# ARKnew.net
KiCad netlist of a schematic drawn in EAGLE
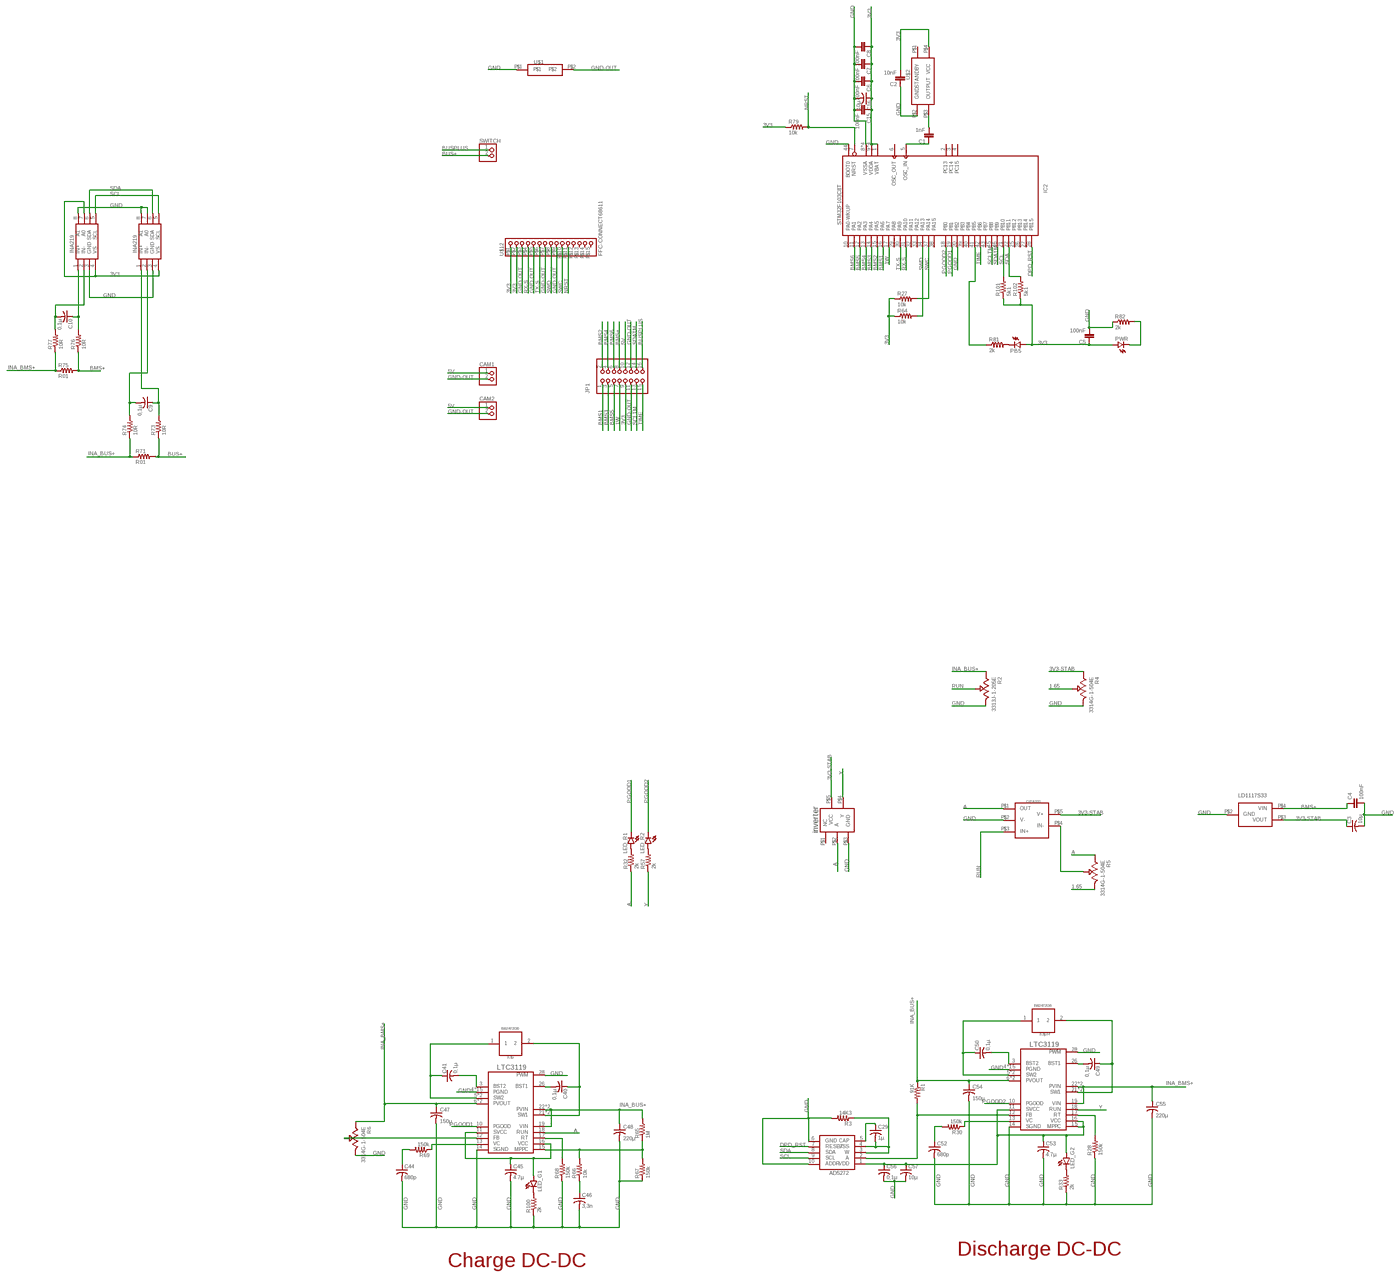
[diagram p0: schematic, sheet 1, overview]
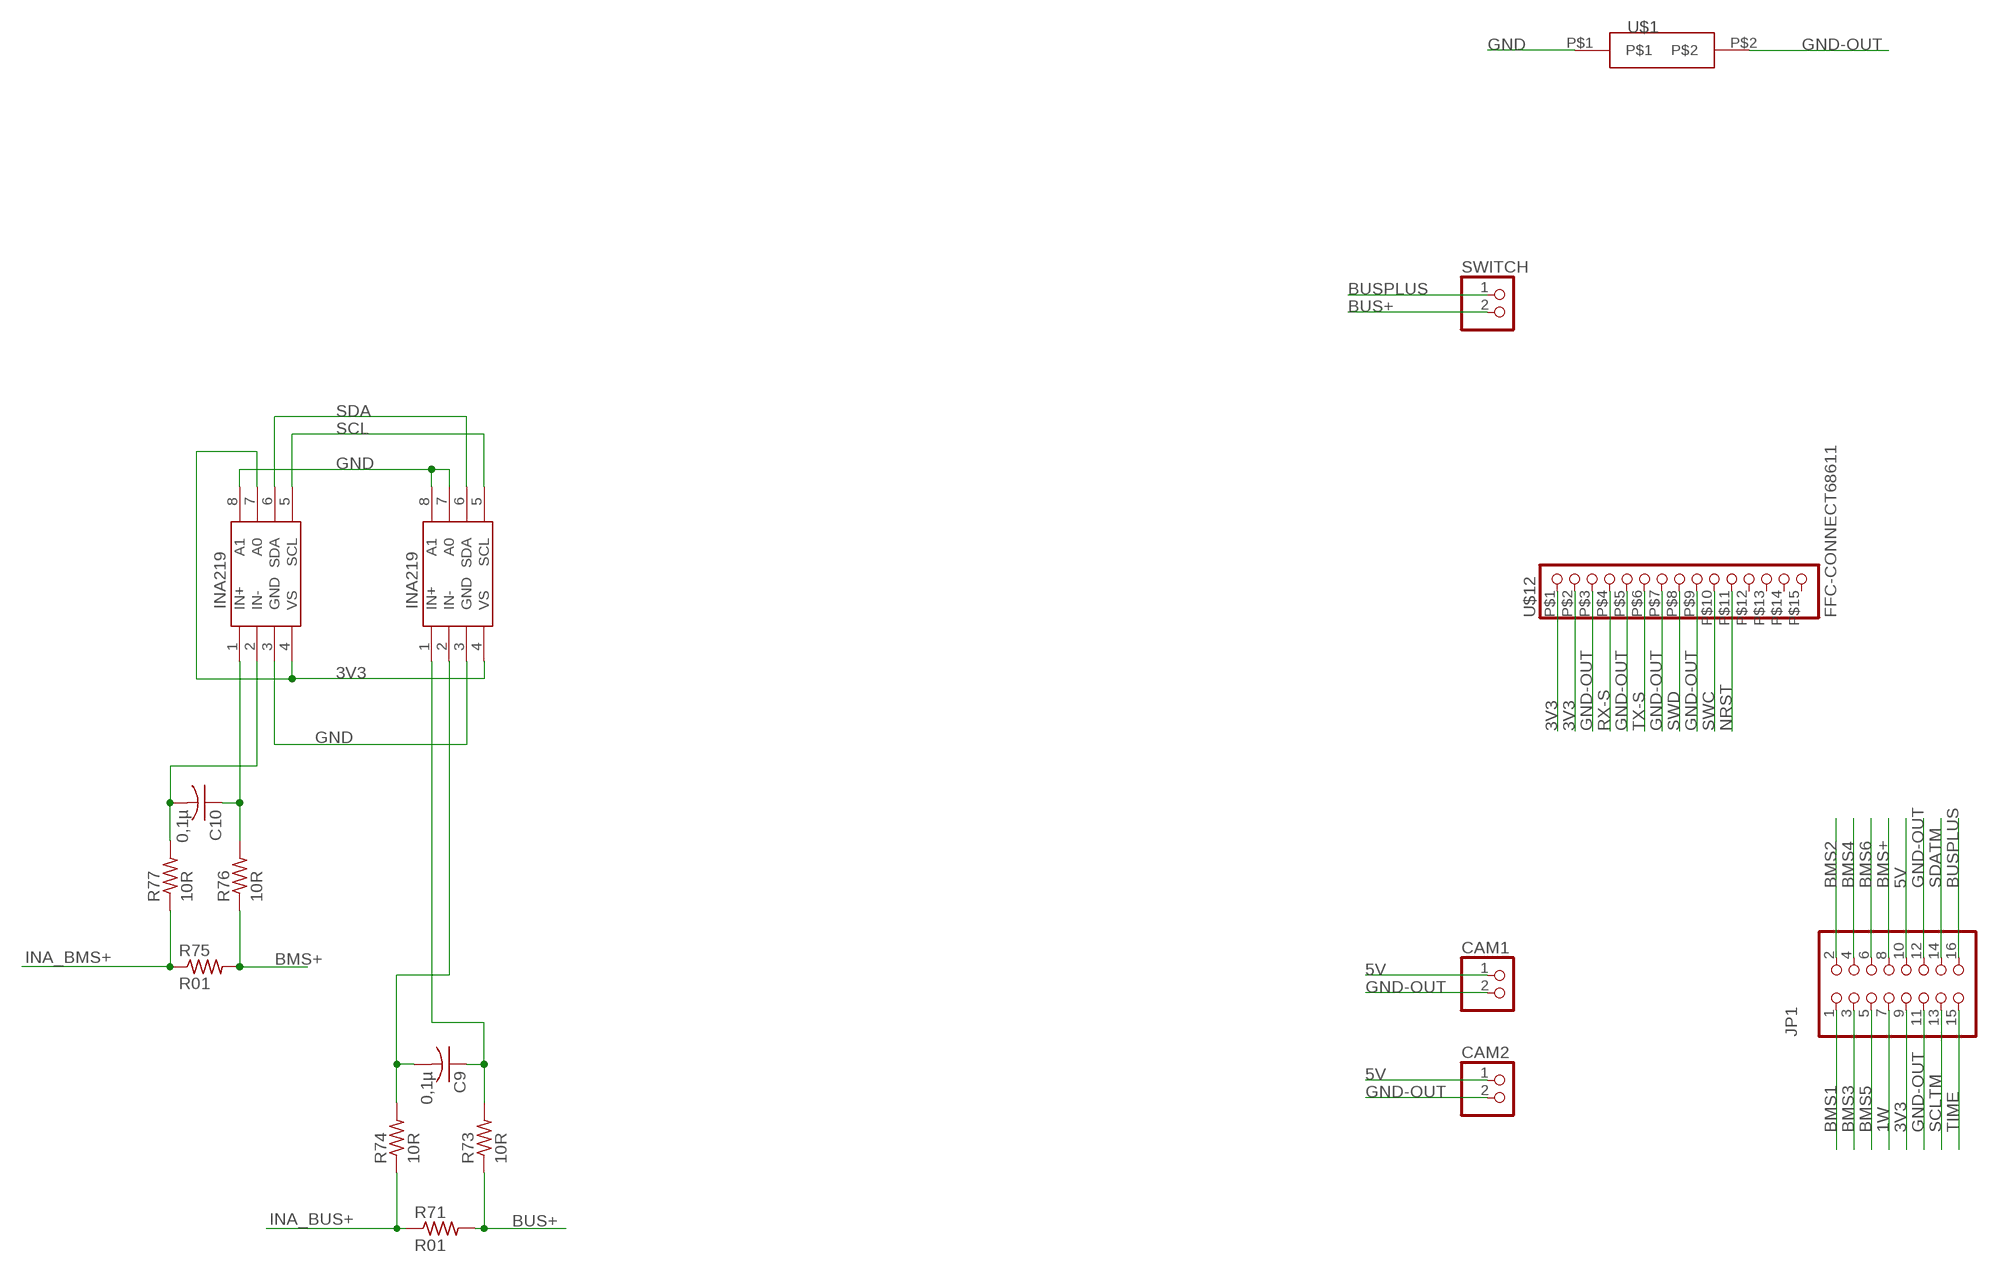
[diagram p1: schematic, sheet 1, part 1 of 4]
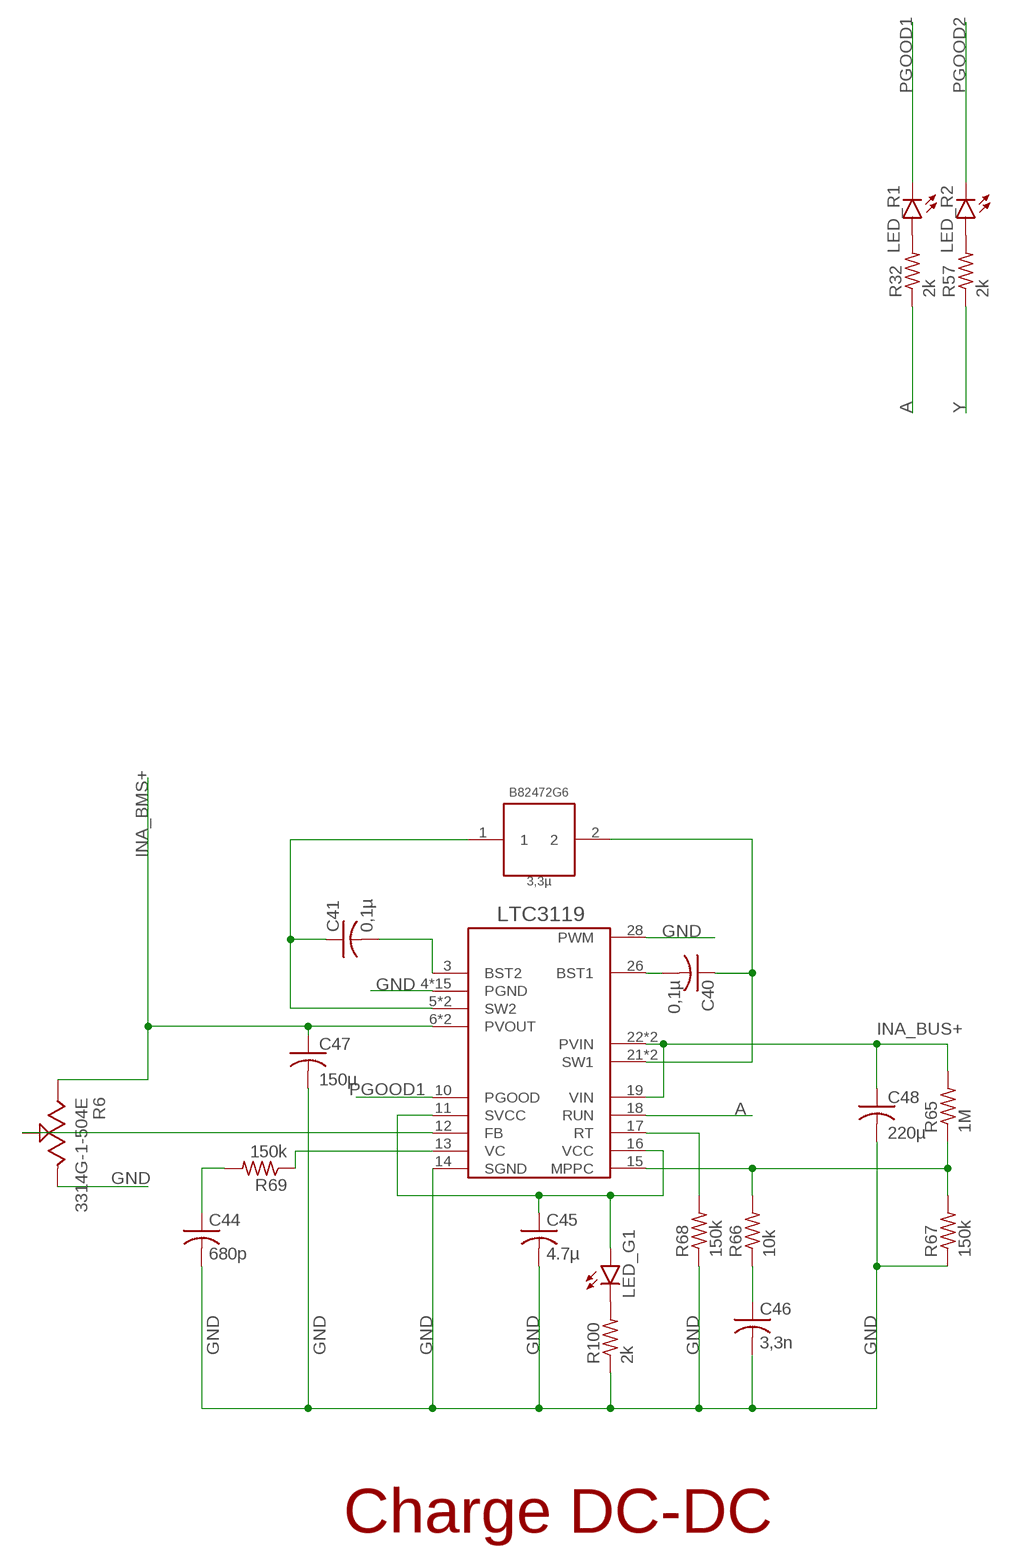
[diagram p2: schematic, sheet 1, part 2 of 4]
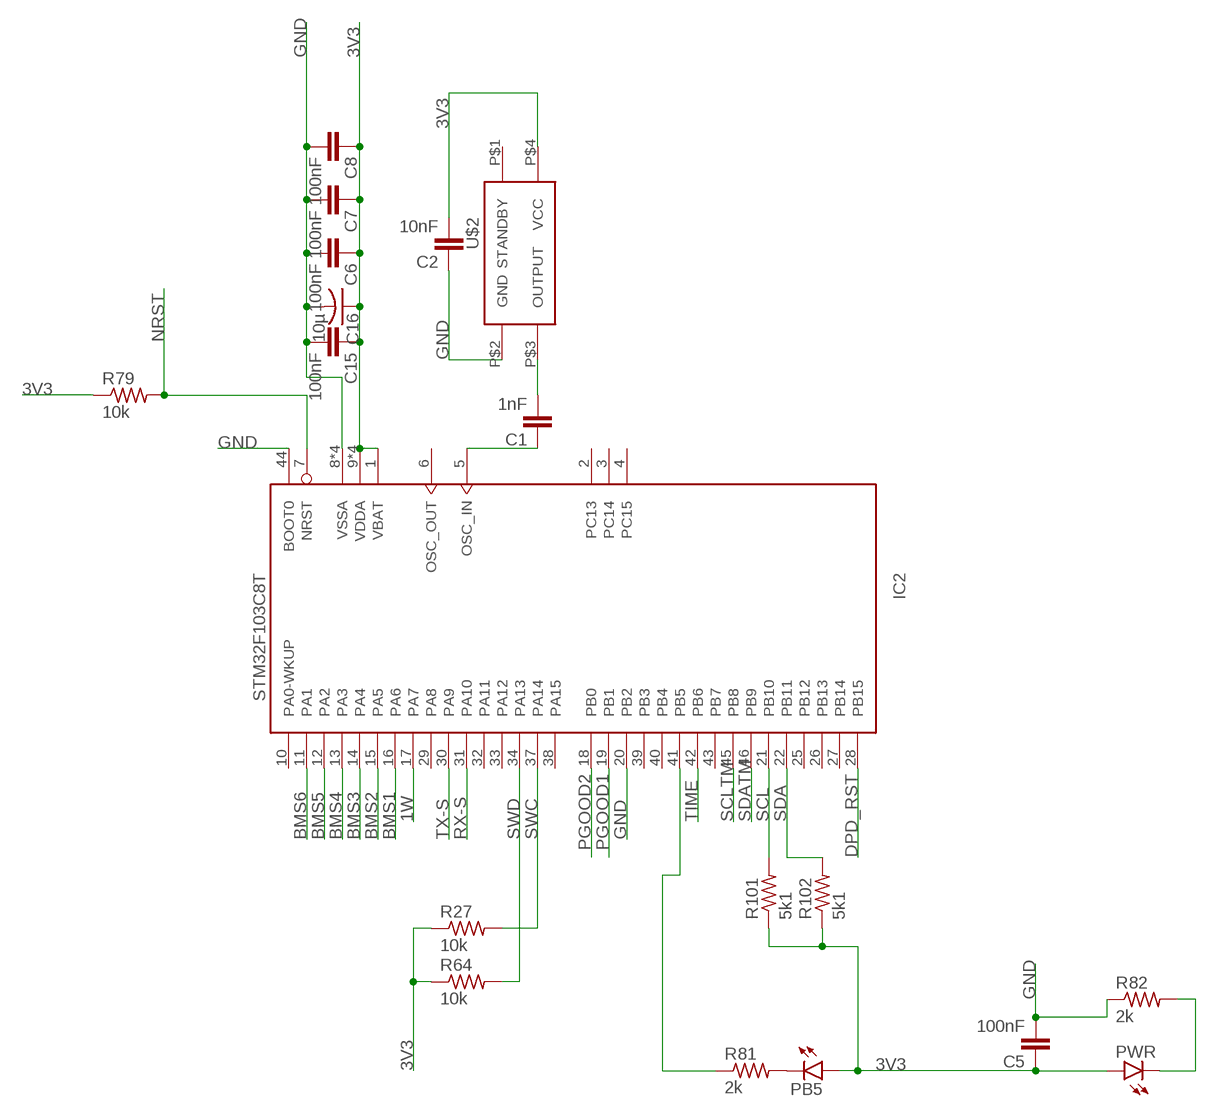
[diagram p3: schematic, sheet 1, part 3 of 4]
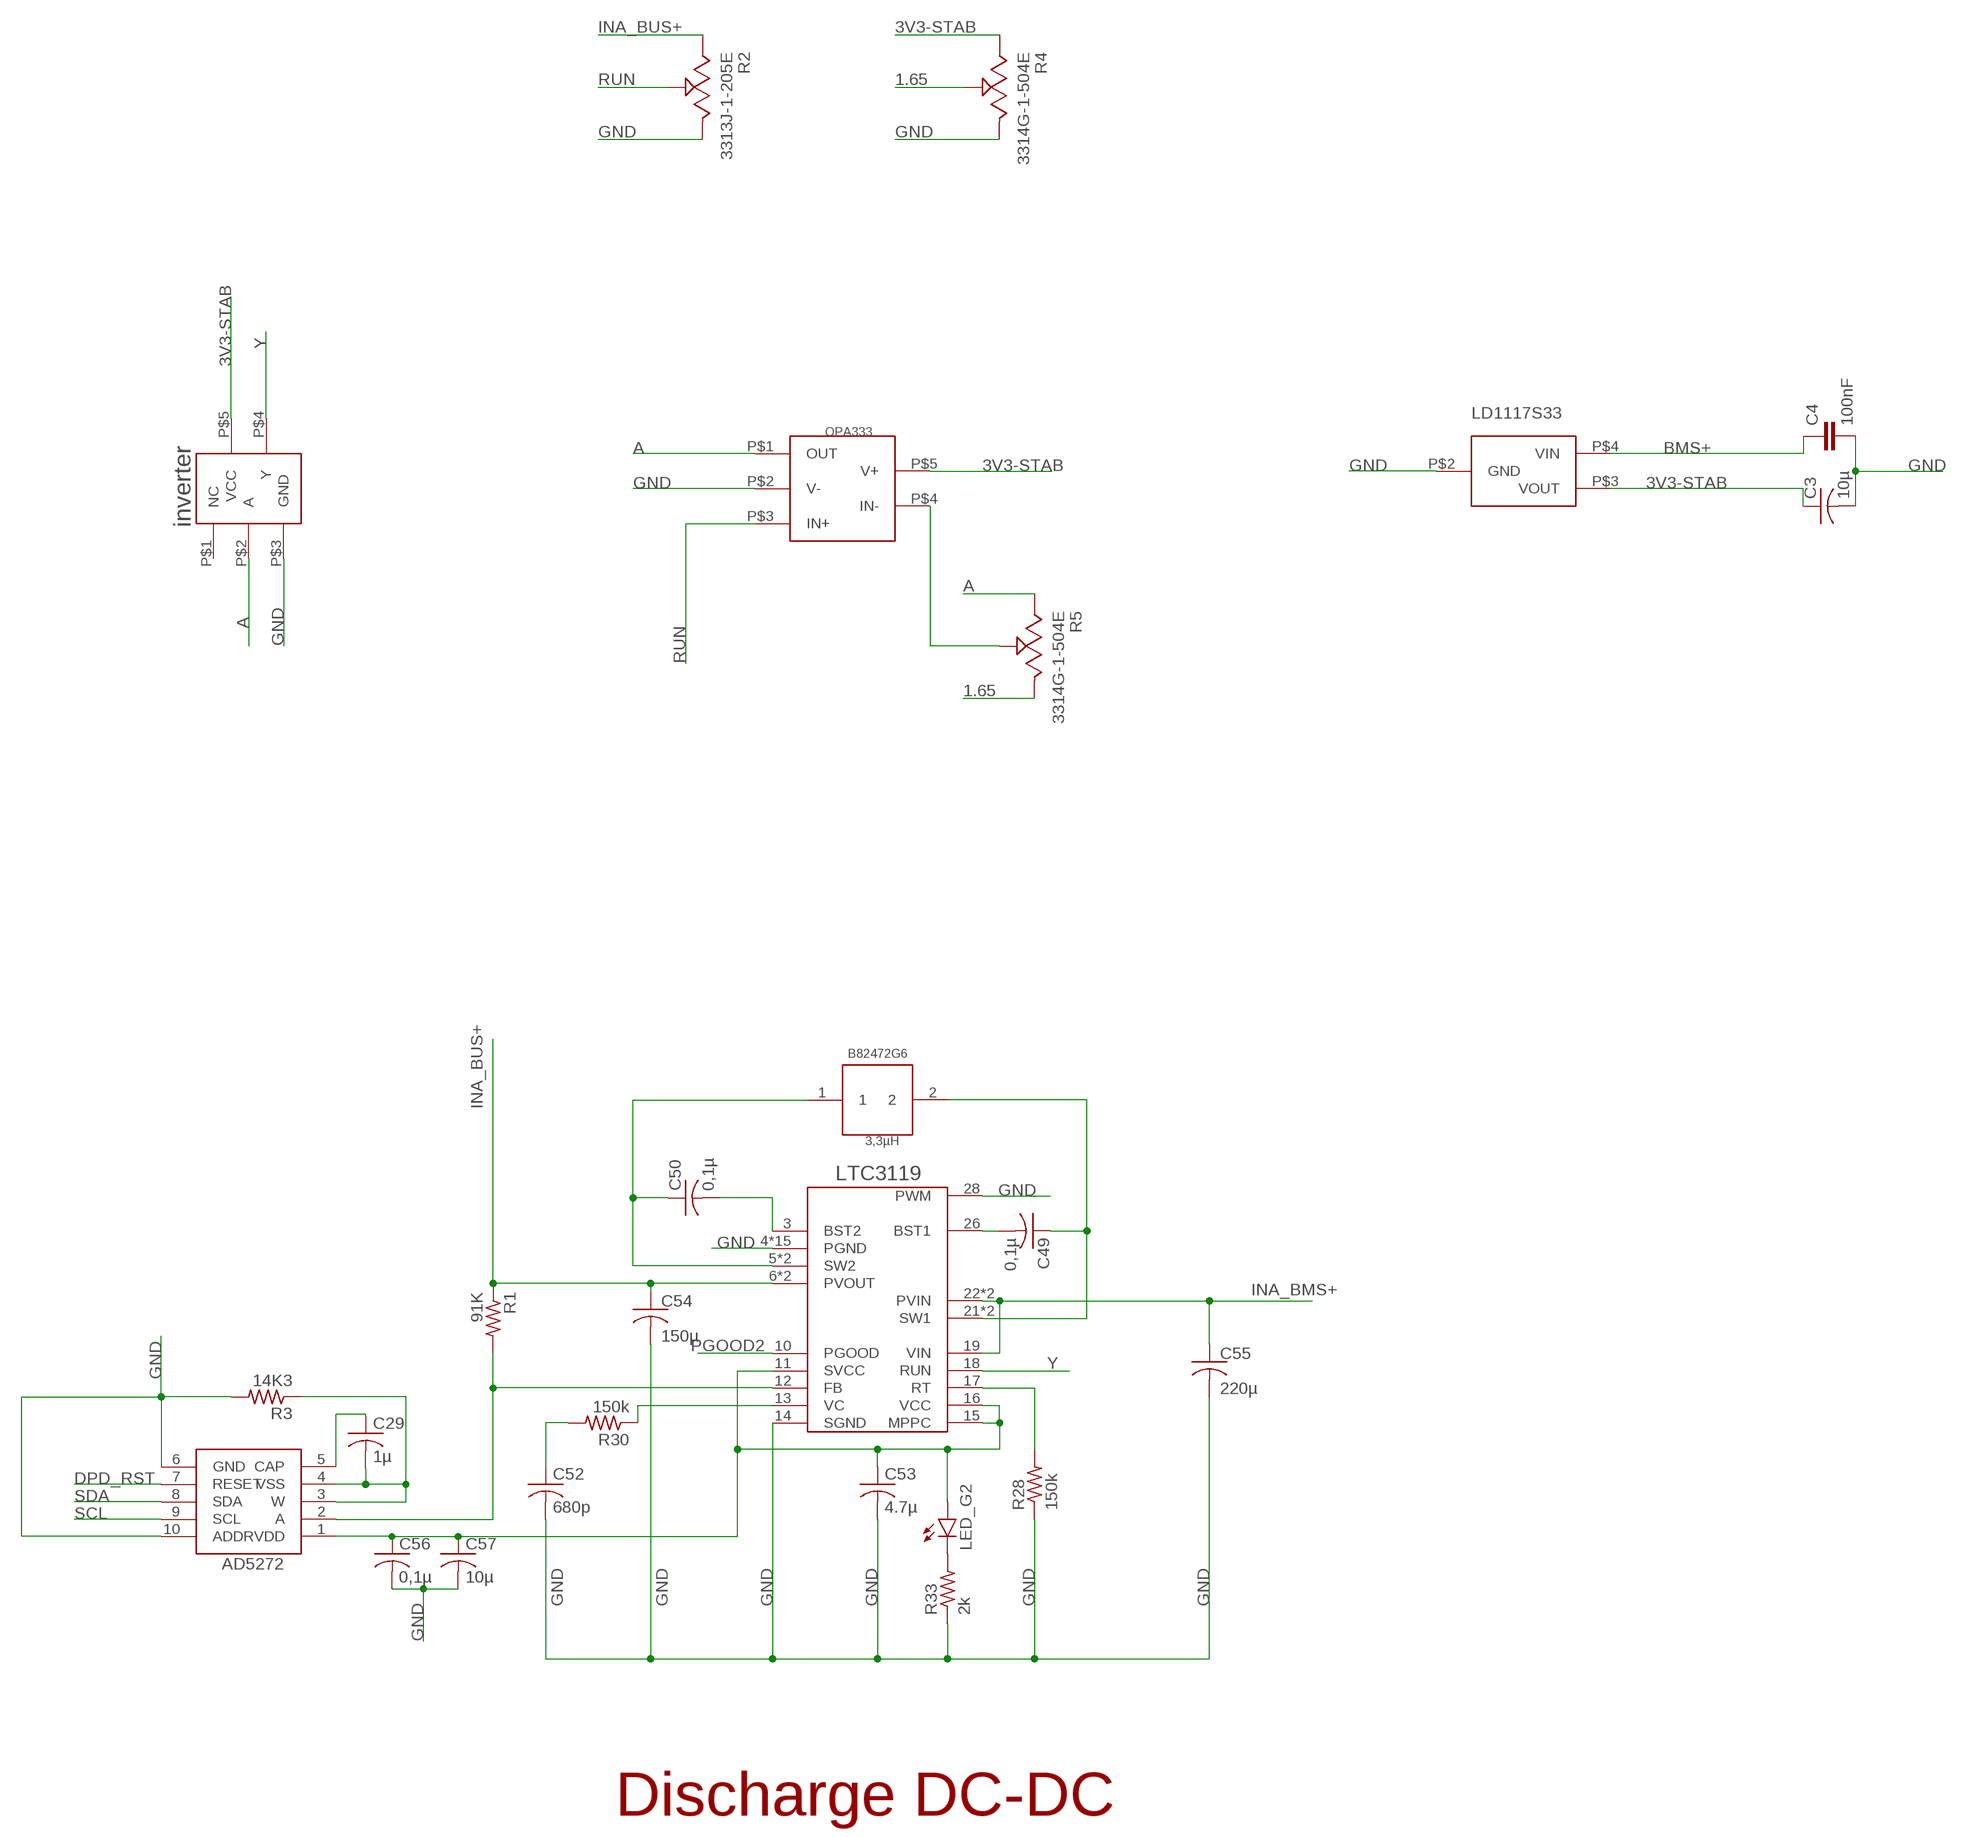
[diagram p4: schematic, sheet 1, part 4 of 4]

(export (version "E")
  (design (tool "Eeschema 10.0.6"))
  (components
    (comp (ref "3,3µH")
      (value "3,3µ")
      (footprint "eagle-import:B82472G6")
      (libsource (lib "eagle-import") (part "B82472G6"))
    )
    (comp (ref "3,3µH1")
      (value "3,3µH")
      (footprint "eagle-import:B82472G6")
      (libsource (lib "eagle-import") (part "B82472G6"))
    )
    (comp (ref "AD5272#2")
      (value "AD5272")
      (footprint "eagle-import:MSOP10")
      (libsource (lib "eagle-import") (part "AD5272"))
    )
    (comp (ref "C1")
      (value "1nF")
      (footprint "eagle-import:C0603")
      (libsource (lib "eagle-import") (part "C-EUC0603"))
    )
    (comp (ref "C2")
      (value "10nF")
      (footprint "eagle-import:C0603")
      (libsource (lib "eagle-import") (part "C-EUC0603"))
    )
    (comp (ref "C3")
      (value "10µ")
      (footprint "eagle-import:C1206")
      (libsource (lib "eagle-import") (part "C-USC1206"))
    )
    (comp (ref "C4")
      (value "100nF")
      (footprint "eagle-import:C0603")
      (libsource (lib "eagle-import") (part "C-EUC0603"))
    )
    (comp (ref "C5")
      (value "100nF")
      (footprint "eagle-import:C0603")
      (libsource (lib "eagle-import") (part "C-EUC0603"))
    )
    (comp (ref "C6")
      (value "100nF")
      (footprint "eagle-import:C0603")
      (libsource (lib "eagle-import") (part "C-EUC0603"))
    )
    (comp (ref "C7")
      (value "100nF")
      (footprint "eagle-import:C0603")
      (libsource (lib "eagle-import") (part "C-EUC0603"))
    )
    (comp (ref "C8")
      (value "100nF")
      (footprint "eagle-import:C0603")
      (libsource (lib "eagle-import") (part "C-EUC0603"))
    )
    (comp (ref "C9")
      (value "0,1µ")
      (footprint "eagle-import:C0603")
      (libsource (lib "eagle-import") (part "C-USC0603"))
    )
    (comp (ref "C10")
      (value "0,1µ")
      (footprint "eagle-import:C0603")
      (libsource (lib "eagle-import") (part "C-USC0603"))
    )
    (comp (ref "C15")
      (value "100nF")
      (footprint "eagle-import:C0603")
      (libsource (lib "eagle-import") (part "C-EUC0603"))
    )
    (comp (ref "C16")
      (value "10µ")
      (footprint "eagle-import:C1206")
      (libsource (lib "eagle-import") (part "C-USC1206"))
    )
    (comp (ref "C29")
      (value "1µ")
      (footprint "eagle-import:C0603")
      (libsource (lib "eagle-import") (part "C-USC0603"))
    )
    (comp (ref "C40")
      (value "0,1µ")
      (footprint "eagle-import:C0603")
      (libsource (lib "eagle-import") (part "C-USC0603"))
    )
    (comp (ref "C41")
      (value "0,1µ")
      (footprint "eagle-import:C0603")
      (libsource (lib "eagle-import") (part "C-USC0603"))
    )
    (comp (ref "C44")
      (value "680p")
      (footprint "eagle-import:C0603")
      (libsource (lib "eagle-import") (part "C-USC0603"))
    )
    (comp (ref "C45")
      (value "4.7µ")
      (footprint "eagle-import:C1206")
      (libsource (lib "eagle-import") (part "C-USC1206"))
    )
    (comp (ref "C46")
      (value "3,3n")
      (footprint "eagle-import:C0603")
      (libsource (lib "eagle-import") (part "C-USC0603"))
    )
    (comp (ref "C47")
      (value "150µ")
      (footprint "eagle-import:ECAP150-CMD")
      (libsource (lib "eagle-import") (part "ECAPECAP150"))
    )
    (comp (ref "C48")
      (value "220µ")
      (footprint "eagle-import:ECAP220-CMD")
      (libsource (lib "eagle-import") (part "ECAPECAP220"))
    )
    (comp (ref "C49")
      (value "0,1µ")
      (footprint "eagle-import:C0603")
      (libsource (lib "eagle-import") (part "C-USC0603"))
    )
    (comp (ref "C50")
      (value "0,1µ")
      (footprint "eagle-import:C0603")
      (libsource (lib "eagle-import") (part "C-USC0603"))
    )
    (comp (ref "C52")
      (value "680p")
      (footprint "eagle-import:C0603")
      (libsource (lib "eagle-import") (part "C-USC0603"))
    )
    (comp (ref "C53")
      (value "4.7µ")
      (footprint "eagle-import:C1206")
      (libsource (lib "eagle-import") (part "C-USC1206"))
    )
    (comp (ref "C54")
      (value "150µ")
      (footprint "eagle-import:ECAP150-CMD")
      (libsource (lib "eagle-import") (part "ECAPECAP150"))
    )
    (comp (ref "C55")
      (value "220µ")
      (footprint "eagle-import:ECAP220-CMD")
      (libsource (lib "eagle-import") (part "ECAPECAP220"))
    )
    (comp (ref "C56")
      (value "0,1µ")
      (footprint "eagle-import:C0603")
      (libsource (lib "eagle-import") (part "C-USC0603"))
    )
    (comp (ref "C57")
      (value "10µ")
      (footprint "eagle-import:C1206")
      (libsource (lib "eagle-import") (part "C-USC1206"))
    )
    (comp (ref "CAM1")
      (value "PINHD-1X2")
      (footprint "eagle-import:1X02")
      (libsource (lib "eagle-import") (part "PINHD-1X2"))
    )
    (comp (ref "CAM2")
      (value "PINHD-1X2")
      (footprint "eagle-import:1X02")
      (libsource (lib "eagle-import") (part "PINHD-1X2"))
    )
    (comp (ref "IC2")
      (value "STM32F103C8T")
      (footprint "eagle-import:LQFP48")
      (libsource (lib "eagle-import") (part "STM32F103CT8"))
    )
    (comp (ref "INA219#1")
      (value "INA219AID")
      (footprint "eagle-import:SOT23-8")
      (libsource (lib "eagle-import") (part "INA219AID"))
    )
    (comp (ref "INVERT")
      (value "INVERTER.")
      (footprint "eagle-import:SC70")
      (libsource (lib "eagle-import") (part "INVERTER."))
    )
    (comp (ref "JP1")
      (value "PINHD-2X8")
      (footprint "eagle-import:2X08")
      (libsource (lib "eagle-import") (part "PINHD-2X8"))
    )
    (comp (ref "LD1117S33")
      (value "LD1117S33")
      (footprint "eagle-import:SOT223")
      (libsource (lib "eagle-import") (part "LD1117S33"))
    )
    (comp (ref "LED_G1")
      (value "LEDCHIPLED_0603")
      (footprint "eagle-import:CHIPLED_0603")
      (libsource (lib "eagle-import") (part "LEDCHIPLED_0603"))
    )
    (comp (ref "LED_G2")
      (value "LEDCHIPLED_0603")
      (footprint "eagle-import:CHIPLED_0603")
      (libsource (lib "eagle-import") (part "LEDCHIPLED_0603"))
    )
    (comp (ref "LED_R1")
      (value "LEDCHIPLED_0603")
      (footprint "eagle-import:CHIPLED_0603")
      (libsource (lib "eagle-import") (part "LEDCHIPLED_0603"))
    )
    (comp (ref "LED_R2")
      (value "LEDCHIPLED_0603")
      (footprint "eagle-import:CHIPLED_0603")
      (libsource (lib "eagle-import") (part "LEDCHIPLED_0603"))
    )
    (comp (ref "OPA")
      (value "OPA333")
      (footprint "eagle-import:SOT23-5")
      (libsource (lib "eagle-import") (part "OPA333"))
    )
    (comp (ref "PB5")
      (value "LEDCHIPLED_0603")
      (footprint "eagle-import:CHIPLED_0603")
      (libsource (lib "eagle-import") (part "LEDCHIPLED_0603"))
    )
    (comp (ref "PWR")
      (value "LEDCHIPLED_0603")
      (footprint "eagle-import:CHIPLED_0603")
      (libsource (lib "eagle-import") (part "LEDCHIPLED_0603"))
    )
    (comp (ref "R1")
      (value "91K")
      (footprint "eagle-import:R0603")
      (libsource (lib "eagle-import") (part "resistor_R-US_R0603"))
    )
    (comp (ref "R2")
      (value "3313J-1-205E")
      (footprint "eagle-import:TRIM_3313J-1-205E")
      (fields (field (name "MF") "Bourns") (field (name "MP") "3313J-1-104E"))
      (libsource (lib "eagle-import") (part "3313J-1-205E"))
    )
    (comp (ref "R3")
      (value "14K3")
      (footprint "eagle-import:R0603")
      (libsource (lib "eagle-import") (part "resistor_R-US_R0603"))
    )
    (comp (ref "R4")
      (value "3314G-1-504E")
      (footprint "eagle-import:TRIM_3314G-1-504E")
      (libsource (lib "eagle-import") (part "3314G-1-504E"))
    )
    (comp (ref "R5")
      (value "3314G-1-504E")
      (footprint "eagle-import:TRIM_3314G-1-504E")
      (libsource (lib "eagle-import") (part "3314G-1-504E"))
    )
    (comp (ref "R6")
      (value "3314G-1-504E")
      (footprint "eagle-import:TRIM_3314G-1-504E")
      (libsource (lib "eagle-import") (part "3314G-1-504E"))
    )
    (comp (ref "R27")
      (value "10k")
      (footprint "eagle-import:R0603")
      (libsource (lib "eagle-import") (part "resistor_R-US_R0603"))
    )
    (comp (ref "R28")
      (value "150k")
      (footprint "eagle-import:R0603")
      (libsource (lib "eagle-import") (part "resistor_R-US_R0603"))
    )
    (comp (ref "R30")
      (value "150k")
      (footprint "eagle-import:R0603")
      (libsource (lib "eagle-import") (part "resistor_R-US_R0603"))
    )
    (comp (ref "R32")
      (value "2k")
      (footprint "eagle-import:R0603")
      (libsource (lib "eagle-import") (part "resistor_R-US_R0603"))
    )
    (comp (ref "R33")
      (value "2k")
      (footprint "eagle-import:R0603")
      (libsource (lib "eagle-import") (part "resistor_R-US_R0603"))
    )
    (comp (ref "R57")
      (value "2k")
      (footprint "eagle-import:R0603")
      (libsource (lib "eagle-import") (part "resistor_R-US_R0603"))
    )
    (comp (ref "R64")
      (value "10k")
      (footprint "eagle-import:R0603")
      (libsource (lib "eagle-import") (part "resistor_R-US_R0603"))
    )
    (comp (ref "R65")
      (value "1M")
      (footprint "eagle-import:R0603")
      (libsource (lib "eagle-import") (part "resistor_R-US_R0603"))
    )
    (comp (ref "R66")
      (value "10k")
      (footprint "eagle-import:R0603")
      (libsource (lib "eagle-import") (part "resistor_R-US_R0603"))
    )
    (comp (ref "R67")
      (value "150k")
      (footprint "eagle-import:R0603")
      (libsource (lib "eagle-import") (part "resistor_R-US_R0603"))
    )
    (comp (ref "R68")
      (value "150k")
      (footprint "eagle-import:R0603")
      (libsource (lib "eagle-import") (part "resistor_R-US_R0603"))
    )
    (comp (ref "R69")
      (value "150k")
      (footprint "eagle-import:R0603")
      (libsource (lib "eagle-import") (part "resistor_R-US_R0603"))
    )
    (comp (ref "R71")
      (value "R01")
      (footprint "eagle-import:R2512")
      (libsource (lib "eagle-import") (part "R-US_R2512"))
    )
    (comp (ref "R73")
      (value "10R")
      (footprint "eagle-import:R0603")
      (libsource (lib "eagle-import") (part "resistor_R-US_R0603"))
    )
    (comp (ref "R74")
      (value "10R")
      (footprint "eagle-import:R0603")
      (libsource (lib "eagle-import") (part "resistor_R-US_R0603"))
    )
    (comp (ref "R75")
      (value "R01")
      (footprint "eagle-import:R2512")
      (libsource (lib "eagle-import") (part "R-US_R2512"))
    )
    (comp (ref "R76")
      (value "10R")
      (footprint "eagle-import:R0603")
      (libsource (lib "eagle-import") (part "resistor_R-US_R0603"))
    )
    (comp (ref "R77")
      (value "10R")
      (footprint "eagle-import:R0603")
      (libsource (lib "eagle-import") (part "resistor_R-US_R0603"))
    )
    (comp (ref "R79")
      (value "10k")
      (footprint "eagle-import:R0603")
      (libsource (lib "eagle-import") (part "resistor_R-US_R0603"))
    )
    (comp (ref "R81")
      (value "2k")
      (footprint "eagle-import:R0603")
      (libsource (lib "eagle-import") (part "resistor_R-US_R0603"))
    )
    (comp (ref "R82")
      (value "2k")
      (footprint "eagle-import:R0603")
      (libsource (lib "eagle-import") (part "resistor_R-US_R0603"))
    )
    (comp (ref "R100")
      (value "2k")
      (footprint "eagle-import:R0603")
      (libsource (lib "eagle-import") (part "resistor_R-US_R0603"))
    )
    (comp (ref "R101")
      (value "5k1")
      (footprint "eagle-import:R0603")
      (libsource (lib "eagle-import") (part "resistor_R-US_R0603"))
    )
    (comp (ref "R102")
      (value "5k1")
      (footprint "eagle-import:R0603")
      (libsource (lib "eagle-import") (part "resistor_R-US_R0603"))
    )
    (comp (ref "SWITCH")
      (value "PINHD-1X2")
      (footprint "eagle-import:1X02")
      (libsource (lib "eagle-import") (part "PINHD-1X2"))
    )
    (comp (ref "U$1")
      (value "MF-R400")
      (footprint "eagle-import:MF-R400")
      (libsource (lib "eagle-import") (part "MF-R400"))
    )
    (comp (ref "U$2")
      (value "Q24")
      (footprint "eagle-import:Q24")
      (libsource (lib "eagle-import") (part "Q24"))
    )
    (comp (ref "U$12")
      (value "FFC-CONNECT68611")
      (footprint "eagle-import:68611")
      (libsource (lib "eagle-import") (part "FFC-CONNECT68611"))
    )
    (comp (ref "U$23")
      (value "LTC31191")
      (footprint "eagle-import:LTC3119+VIA")
      (libsource (lib "eagle-import") (part "LTC31191"))
    )
    (comp (ref "U$57")
      (value "INA219AID")
      (footprint "eagle-import:SOT23-8")
      (libsource (lib "eagle-import") (part "INA219AID"))
    )
    (comp (ref "U$59")
      (value "LTC31191")
      (footprint "eagle-import:LTC3119+VIA")
      (libsource (lib "eagle-import") (part "LTC31191"))
    )
  )
  (nets
    (net (code "1") (name "/1.65") (class "Default")
      (node (ref "R4") (pin "2") (pinfunction "WIPER_2") (pintype "passive"))
      (node (ref "R5") (pin "3") (pinfunction "CW_3") (pintype "passive"))
    )
    (net (code "2") (name "/1W") (class "Default")
      (node (ref "IC2") (pin "17") (pinfunction "PA7_17") (pintype "bidirectional"))
      (node (ref "JP1") (pin "7") (pinfunction "7_7") (pintype "passive"))
    )
    (net (code "3") (name "/3V3") (class "Default")
      (node (ref "C15") (pin "1") (pinfunction "1_1") (pintype "passive"))
      (node (ref "C16") (pin "1") (pinfunction "1_1") (pintype "passive"))
      (node (ref "C2") (pin "2") (pinfunction "2_2") (pintype "passive"))
      (node (ref "C5") (pin "1") (pinfunction "1_1") (pintype "passive"))
      (node (ref "C6") (pin "1") (pinfunction "1_1") (pintype "passive"))
      (node (ref "C7") (pin "1") (pinfunction "1_1") (pintype "passive"))
      (node (ref "C8") (pin "1") (pinfunction "1_1") (pintype "passive"))
      (node (ref "IC2") (pin "1") (pinfunction "VBAT_1") (pintype "power_in"))
      (node (ref "IC2") (pin "24") (pinfunction "VDDA_24") (pintype "power_in"))
      (node (ref "IC2") (pin "36") (pinfunction "VDDA_36") (pintype "power_in"))
      (node (ref "IC2") (pin "48") (pinfunction "VDDA_48") (pintype "power_in"))
      (node (ref "IC2") (pin "9") (pinfunction "VDDA_9") (pintype "power_in"))
      (node (ref "INA219#1") (pin "4") (pinfunction "VS_4") (pintype "bidirectional"))
      (node (ref "JP1") (pin "9") (pinfunction "9_9") (pintype "passive"))
      (node (ref "PB5") (pin "A") (pinfunction "A_A") (pintype "passive"))
      (node (ref "PWR") (pin "A") (pinfunction "A_A") (pintype "passive"))
      (node (ref "R101") (pin "1") (pinfunction "1_1") (pintype "passive"))
      (node (ref "R102") (pin "1") (pinfunction "1_1") (pintype "passive"))
      (node (ref "R27") (pin "1") (pinfunction "1_1") (pintype "passive"))
      (node (ref "R64") (pin "1") (pinfunction "1_1") (pintype "passive"))
      (node (ref "R79") (pin "1") (pinfunction "1_1") (pintype "passive"))
      (node (ref "U$12") (pin "P$1") (pinfunction "1_P$1") (pintype "passive"))
      (node (ref "U$12") (pin "P$2") (pinfunction "2_P$2") (pintype "passive"))
      (node (ref "U$2") (pin "P$4") (pinfunction "VCC_P$4") (pintype "bidirectional"))
      (node (ref "U$57") (pin "4") (pinfunction "VS_4") (pintype "bidirectional"))
      (node (ref "U$57") (pin "7") (pinfunction "A0_7") (pintype "bidirectional"))
    )
    (net (code "4") (name "/3V3-STAB") (class "Default")
      (node (ref "C3") (pin "1") (pinfunction "1_1") (pintype "passive"))
      (node (ref "INVERT") (pin "P$5") (pinfunction "VCC_P$5") (pintype "bidirectional"))
      (node (ref "LD1117S33") (pin "P$3") (pinfunction "VOUT_P$3") (pintype "bidirectional"))
      (node (ref "OPA") (pin "P$5") (pinfunction "V+_P$5") (pintype "bidirectional"))
      (node (ref "R4") (pin "1") (pinfunction "CCW_1") (pintype "passive"))
    )
    (net (code "5") (name "/5V") (class "Default")
      (node (ref "CAM1") (pin "1") (pinfunction "1_1") (pintype "passive"))
      (node (ref "CAM2") (pin "1") (pinfunction "1_1") (pintype "passive"))
      (node (ref "JP1") (pin "10") (pinfunction "10_10") (pintype "passive"))
    )
    (net (code "6") (name "/A") (class "Default")
      (node (ref "INVERT") (pin "P$2") (pinfunction "A_P$2") (pintype "bidirectional"))
      (node (ref "OPA") (pin "P$1") (pinfunction "OUT_P$1") (pintype "bidirectional"))
      (node (ref "R32") (pin "1") (pinfunction "1_1") (pintype "passive"))
      (node (ref "R5") (pin "1") (pinfunction "CCW_1") (pintype "passive"))
      (node (ref "U$59") (pin "18") (pinfunction "RUN_18") (pintype "bidirectional"))
    )
    (net (code "7") (name "/BMS+") (class "Default")
      (node (ref "C4") (pin "1") (pinfunction "1_1") (pintype "passive"))
      (node (ref "JP1") (pin "8") (pinfunction "8_8") (pintype "passive"))
      (node (ref "LD1117S33") (pin "P$4") (pinfunction "VIN_P$4") (pintype "bidirectional"))
      (node (ref "R75") (pin "2") (pinfunction "2_2") (pintype "passive"))
      (node (ref "R76") (pin "1") (pinfunction "1_1") (pintype "passive"))
    )
    (net (code "8") (name "/BMS1") (class "Default")
      (node (ref "IC2") (pin "16") (pinfunction "PA6_16") (pintype "bidirectional"))
      (node (ref "JP1") (pin "1") (pinfunction "1_1") (pintype "passive"))
    )
    (net (code "9") (name "/BMS2") (class "Default")
      (node (ref "IC2") (pin "15") (pinfunction "PA5_15") (pintype "bidirectional"))
      (node (ref "JP1") (pin "2") (pinfunction "2_2") (pintype "passive"))
    )
    (net (code "10") (name "/BMS3") (class "Default")
      (node (ref "IC2") (pin "14") (pinfunction "PA4_14") (pintype "bidirectional"))
      (node (ref "JP1") (pin "3") (pinfunction "3_3") (pintype "passive"))
    )
    (net (code "11") (name "/BMS4") (class "Default")
      (node (ref "IC2") (pin "13") (pinfunction "PA3_13") (pintype "bidirectional"))
      (node (ref "JP1") (pin "4") (pinfunction "4_4") (pintype "passive"))
    )
    (net (code "12") (name "/BMS5") (class "Default")
      (node (ref "IC2") (pin "12") (pinfunction "PA2_12") (pintype "bidirectional"))
      (node (ref "JP1") (pin "5") (pinfunction "5_5") (pintype "passive"))
    )
    (net (code "13") (name "/BMS6") (class "Default")
      (node (ref "IC2") (pin "11") (pinfunction "PA1_11") (pintype "bidirectional"))
      (node (ref "JP1") (pin "6") (pinfunction "6_6") (pintype "passive"))
    )
    (net (code "14") (name "/BUS+") (class "Default")
      (node (ref "R71") (pin "2") (pinfunction "2_2") (pintype "passive"))
      (node (ref "R73") (pin "1") (pinfunction "1_1") (pintype "passive"))
      (node (ref "SWITCH") (pin "2") (pinfunction "2_2") (pintype "passive"))
    )
    (net (code "15") (name "/BUSPLUS") (class "Default")
      (node (ref "JP1") (pin "16") (pinfunction "16_16") (pintype "passive"))
      (node (ref "SWITCH") (pin "1") (pinfunction "1_1") (pintype "passive"))
    )
    (net (code "16") (name "/DPD_RST") (class "Default")
      (node (ref "AD5272#2") (pin "7") (pinfunction "RESET_7") (pintype "bidirectional"))
      (node (ref "IC2") (pin "28") (pinfunction "PB15_28") (pintype "bidirectional"))
    )
    (net (code "17") (name "/GND") (class "Default")
      (node (ref "AD5272#2") (pin "10") (pinfunction "ADDR_10") (pintype "bidirectional"))
      (node (ref "AD5272#2") (pin "6") (pinfunction "GND_6") (pintype "bidirectional"))
      (node (ref "C15") (pin "2") (pinfunction "2_2") (pintype "passive"))
      (node (ref "C16") (pin "2") (pinfunction "2_2") (pintype "passive"))
      (node (ref "C2") (pin "1") (pinfunction "1_1") (pintype "passive"))
      (node (ref "C3") (pin "2") (pinfunction "2_2") (pintype "passive"))
      (node (ref "C4") (pin "2") (pinfunction "2_2") (pintype "passive"))
      (node (ref "C44") (pin "2") (pinfunction "2_2") (pintype "passive"))
      (node (ref "C45") (pin "2") (pinfunction "2_2") (pintype "passive"))
      (node (ref "C46") (pin "2") (pinfunction "2_2") (pintype "passive"))
      (node (ref "C47") (pin "P$2") (pinfunction "2_P$2") (pintype "passive"))
      (node (ref "C48") (pin "P$2") (pinfunction "2_P$2") (pintype "passive"))
      (node (ref "C5") (pin "2") (pinfunction "2_2") (pintype "passive"))
      (node (ref "C52") (pin "2") (pinfunction "2_2") (pintype "passive"))
      (node (ref "C53") (pin "2") (pinfunction "2_2") (pintype "passive"))
      (node (ref "C54") (pin "P$2") (pinfunction "2_P$2") (pintype "passive"))
      (node (ref "C55") (pin "P$2") (pinfunction "2_P$2") (pintype "passive"))
      (node (ref "C56") (pin "2") (pinfunction "2_2") (pintype "passive"))
      (node (ref "C57") (pin "2") (pinfunction "2_2") (pintype "passive"))
      (node (ref "C6") (pin "2") (pinfunction "2_2") (pintype "passive"))
      (node (ref "C7") (pin "2") (pinfunction "2_2") (pintype "passive"))
      (node (ref "C8") (pin "2") (pinfunction "2_2") (pintype "passive"))
      (node (ref "IC2") (pin "20") (pinfunction "PB2_20") (pintype "bidirectional"))
      (node (ref "IC2") (pin "23") (pinfunction "VSSA_23") (pintype "power_in"))
      (node (ref "IC2") (pin "35") (pinfunction "VSSA_35") (pintype "power_in"))
      (node (ref "IC2") (pin "44") (pinfunction "BOOT0_44") (pintype "input"))
      (node (ref "IC2") (pin "47") (pinfunction "VSSA_47") (pintype "power_in"))
      (node (ref "IC2") (pin "8") (pinfunction "VSSA_8") (pintype "power_in"))
      (node (ref "INA219#1") (pin "3") (pinfunction "GND_3") (pintype "bidirectional"))
      (node (ref "INA219#1") (pin "7") (pinfunction "A0_7") (pintype "bidirectional"))
      (node (ref "INA219#1") (pin "8") (pinfunction "A1_8") (pintype "bidirectional"))
      (node (ref "INVERT") (pin "P$3") (pinfunction "GND_P$3") (pintype "bidirectional"))
      (node (ref "LD1117S33") (pin "P$2") (pinfunction "GND_P$2") (pintype "bidirectional"))
      (node (ref "OPA") (pin "P$2") (pinfunction "V-_P$2") (pintype "bidirectional"))
      (node (ref "R100") (pin "1") (pinfunction "1_1") (pintype "passive"))
      (node (ref "R2") (pin "3") (pinfunction "CW_3") (pintype "passive"))
      (node (ref "R28") (pin "1") (pinfunction "1_1") (pintype "passive"))
      (node (ref "R3") (pin "2") (pinfunction "2_2") (pintype "passive"))
      (node (ref "R33") (pin "1") (pinfunction "1_1") (pintype "passive"))
      (node (ref "R4") (pin "3") (pinfunction "CW_3") (pintype "passive"))
      (node (ref "R6") (pin "3") (pinfunction "CW_3") (pintype "passive"))
      (node (ref "R67") (pin "1") (pinfunction "1_1") (pintype "passive"))
      (node (ref "R68") (pin "1") (pinfunction "1_1") (pintype "passive"))
      (node (ref "R82") (pin "1") (pinfunction "1_1") (pintype "passive"))
      (node (ref "U$1") (pin "P$1") (pinfunction "P$1_P$1") (pintype "bidirectional"))
      (node (ref "U$2") (pin "P$2") (pinfunction "GND_P$2") (pintype "bidirectional"))
      (node (ref "U$23") (pin "14") (pinfunction "SGND_14") (pintype "bidirectional"))
      (node (ref "U$23") (pin "20") (pinfunction "PGND_20") (pintype "bidirectional"))
      (node (ref "U$23") (pin "25") (pinfunction "PGND_25") (pintype "bidirectional"))
      (node (ref "U$23") (pin "28") (pinfunction "PWM_28") (pintype "bidirectional"))
      (node (ref "U$23") (pin "29") (pinfunction "PGND_29") (pintype "bidirectional"))
      (node (ref "U$23") (pin "4") (pinfunction "PGND_4") (pintype "bidirectional"))
      (node (ref "U$23") (pin "9") (pinfunction "PGND_9") (pintype "bidirectional"))
      (node (ref "U$23") (pin "P$1") (pinfunction "PGND_P$1") (pintype "bidirectional"))
      (node (ref "U$23") (pin "P$10") (pinfunction "PGND_P$10") (pintype "bidirectional"))
      (node (ref "U$23") (pin "P$2") (pinfunction "PGND_P$2") (pintype "bidirectional"))
      (node (ref "U$23") (pin "P$3") (pinfunction "PGND_P$3") (pintype "bidirectional"))
      (node (ref "U$23") (pin "P$4") (pinfunction "PGND_P$4") (pintype "bidirectional"))
      (node (ref "U$23") (pin "P$5") (pinfunction "PGND_P$5") (pintype "bidirectional"))
      (node (ref "U$23") (pin "P$6") (pinfunction "PGND_P$6") (pintype "bidirectional"))
      (node (ref "U$23") (pin "P$7") (pinfunction "PGND_P$7") (pintype "bidirectional"))
      (node (ref "U$23") (pin "P$8") (pinfunction "PGND_P$8") (pintype "bidirectional"))
      (node (ref "U$23") (pin "P$9") (pinfunction "PGND_P$9") (pintype "bidirectional"))
      (node (ref "U$57") (pin "3") (pinfunction "GND_3") (pintype "bidirectional"))
      (node (ref "U$57") (pin "8") (pinfunction "A1_8") (pintype "bidirectional"))
      (node (ref "U$59") (pin "14") (pinfunction "SGND_14") (pintype "bidirectional"))
      (node (ref "U$59") (pin "20") (pinfunction "PGND_20") (pintype "bidirectional"))
      (node (ref "U$59") (pin "25") (pinfunction "PGND_25") (pintype "bidirectional"))
      (node (ref "U$59") (pin "28") (pinfunction "PWM_28") (pintype "bidirectional"))
      (node (ref "U$59") (pin "29") (pinfunction "PGND_29") (pintype "bidirectional"))
      (node (ref "U$59") (pin "4") (pinfunction "PGND_4") (pintype "bidirectional"))
      (node (ref "U$59") (pin "9") (pinfunction "PGND_9") (pintype "bidirectional"))
      (node (ref "U$59") (pin "P$1") (pinfunction "PGND_P$1") (pintype "bidirectional"))
      (node (ref "U$59") (pin "P$10") (pinfunction "PGND_P$10") (pintype "bidirectional"))
      (node (ref "U$59") (pin "P$2") (pinfunction "PGND_P$2") (pintype "bidirectional"))
      (node (ref "U$59") (pin "P$3") (pinfunction "PGND_P$3") (pintype "bidirectional"))
      (node (ref "U$59") (pin "P$4") (pinfunction "PGND_P$4") (pintype "bidirectional"))
      (node (ref "U$59") (pin "P$5") (pinfunction "PGND_P$5") (pintype "bidirectional"))
      (node (ref "U$59") (pin "P$6") (pinfunction "PGND_P$6") (pintype "bidirectional"))
      (node (ref "U$59") (pin "P$7") (pinfunction "PGND_P$7") (pintype "bidirectional"))
      (node (ref "U$59") (pin "P$8") (pinfunction "PGND_P$8") (pintype "bidirectional"))
      (node (ref "U$59") (pin "P$9") (pinfunction "PGND_P$9") (pintype "bidirectional"))
    )
    (net (code "18") (name "/GND-OUT") (class "Default")
      (node (ref "CAM1") (pin "2") (pinfunction "2_2") (pintype "passive"))
      (node (ref "CAM2") (pin "2") (pinfunction "2_2") (pintype "passive"))
      (node (ref "JP1") (pin "11") (pinfunction "11_11") (pintype "passive"))
      (node (ref "JP1") (pin "12") (pinfunction "12_12") (pintype "passive"))
      (node (ref "U$1") (pin "P$2") (pinfunction "P$2_P$2") (pintype "bidirectional"))
      (node (ref "U$12") (pin "P$3") (pinfunction "3_P$3") (pintype "passive"))
      (node (ref "U$12") (pin "P$5") (pinfunction "5_P$5") (pintype "passive"))
      (node (ref "U$12") (pin "P$7") (pinfunction "7_P$7") (pintype "passive"))
      (node (ref "U$12") (pin "P$9") (pinfunction "9_P$9") (pintype "passive"))
    )
    (net (code "19") (name "/INA_BMS+") (class "Default")
      (node (ref "C47") (pin "P$1") (pinfunction "1_P$1") (pintype "passive"))
      (node (ref "C55") (pin "P$1") (pinfunction "1_P$1") (pintype "passive"))
      (node (ref "R6") (pin "1") (pinfunction "CCW_1") (pintype "passive"))
      (node (ref "R75") (pin "1") (pinfunction "1_1") (pintype "passive"))
      (node (ref "R77") (pin "1") (pinfunction "1_1") (pintype "passive"))
      (node (ref "U$23") (pin "19") (pinfunction "VIN_19") (pintype "bidirectional"))
      (node (ref "U$23") (pin "22") (pinfunction "PVIN_22") (pintype "bidirectional"))
      (node (ref "U$23") (pin "23") (pinfunction "PVIN_23") (pintype "bidirectional"))
      (node (ref "U$59") (pin "6") (pinfunction "PVOUT_6") (pintype "bidirectional"))
      (node (ref "U$59") (pin "7") (pinfunction "PVOUT_7") (pintype "bidirectional"))
    )
    (net (code "20") (name "/INA_BUS+") (class "Default")
      (node (ref "C48") (pin "P$1") (pinfunction "1_P$1") (pintype "passive"))
      (node (ref "C54") (pin "P$1") (pinfunction "1_P$1") (pintype "passive"))
      (node (ref "R1") (pin "1") (pinfunction "1_1") (pintype "passive"))
      (node (ref "R2") (pin "1") (pinfunction "CCW_1") (pintype "passive"))
      (node (ref "R65") (pin "2") (pinfunction "2_2") (pintype "passive"))
      (node (ref "R71") (pin "1") (pinfunction "1_1") (pintype "passive"))
      (node (ref "R74") (pin "1") (pinfunction "1_1") (pintype "passive"))
      (node (ref "U$23") (pin "6") (pinfunction "PVOUT_6") (pintype "bidirectional"))
      (node (ref "U$23") (pin "7") (pinfunction "PVOUT_7") (pintype "bidirectional"))
      (node (ref "U$59") (pin "19") (pinfunction "VIN_19") (pintype "bidirectional"))
      (node (ref "U$59") (pin "22") (pinfunction "PVIN_22") (pintype "bidirectional"))
      (node (ref "U$59") (pin "23") (pinfunction "PVIN_23") (pintype "bidirectional"))
    )
    (net (code "21") (name "/NRST") (class "Default")
      (node (ref "IC2") (pin "7") (pinfunction "NRST_7") (pintype "bidirectional"))
      (node (ref "R79") (pin "2") (pinfunction "2_2") (pintype "passive"))
      (node (ref "U$12") (pin "P$11") (pinfunction "11_P$11") (pintype "passive"))
    )
    (net (code "22") (name "/PGOOD1") (class "Default")
      (node (ref "IC2") (pin "19") (pinfunction "PB1_19") (pintype "bidirectional"))
      (node (ref "LED_R1") (pin "C") (pinfunction "C_C") (pintype "passive"))
      (node (ref "U$59") (pin "10") (pinfunction "PGOOD_10") (pintype "bidirectional"))
    )
    (net (code "23") (name "/PGOOD2") (class "Default")
      (node (ref "IC2") (pin "18") (pinfunction "PB0_18") (pintype "bidirectional"))
      (node (ref "LED_R2") (pin "C") (pinfunction "C_C") (pintype "passive"))
      (node (ref "U$23") (pin "10") (pinfunction "PGOOD_10") (pintype "bidirectional"))
    )
    (net (code "24") (name "/RUN") (class "Default")
      (node (ref "OPA") (pin "P$3") (pinfunction "IN+_P$3") (pintype "bidirectional"))
      (node (ref "R2") (pin "2") (pinfunction "WIPER_2") (pintype "passive"))
    )
    (net (code "25") (name "/RX-S") (class "Default")
      (node (ref "IC2") (pin "31") (pinfunction "PA10_31") (pintype "bidirectional"))
      (node (ref "U$12") (pin "P$4") (pinfunction "4_P$4") (pintype "passive"))
    )
    (net (code "26") (name "/SCL") (class "Default")
      (node (ref "AD5272#2") (pin "9") (pinfunction "SCL_9") (pintype "bidirectional"))
      (node (ref "IC2") (pin "21") (pinfunction "PB10_21") (pintype "bidirectional"))
      (node (ref "INA219#1") (pin "5") (pinfunction "SCL_5") (pintype "bidirectional"))
      (node (ref "R101") (pin "2") (pinfunction "2_2") (pintype "passive"))
      (node (ref "U$57") (pin "5") (pinfunction "SCL_5") (pintype "bidirectional"))
    )
    (net (code "27") (name "/SCLTM") (class "Default")
      (node (ref "IC2") (pin "45") (pinfunction "PB8_45") (pintype "bidirectional"))
      (node (ref "JP1") (pin "13") (pinfunction "13_13") (pintype "passive"))
    )
    (net (code "28") (name "/SDA") (class "Default")
      (node (ref "AD5272#2") (pin "8") (pinfunction "SDA_8") (pintype "bidirectional"))
      (node (ref "IC2") (pin "22") (pinfunction "PB11_22") (pintype "bidirectional"))
      (node (ref "INA219#1") (pin "6") (pinfunction "SDA_6") (pintype "bidirectional"))
      (node (ref "R102") (pin "2") (pinfunction "2_2") (pintype "passive"))
      (node (ref "U$57") (pin "6") (pinfunction "SDA_6") (pintype "bidirectional"))
    )
    (net (code "29") (name "/SDATM") (class "Default")
      (node (ref "IC2") (pin "46") (pinfunction "PB9_46") (pintype "bidirectional"))
      (node (ref "JP1") (pin "14") (pinfunction "14_14") (pintype "passive"))
    )
    (net (code "30") (name "/SWC") (class "Default")
      (node (ref "IC2") (pin "37") (pinfunction "PA14_37") (pintype "bidirectional"))
      (node (ref "R27") (pin "2") (pinfunction "2_2") (pintype "passive"))
      (node (ref "U$12") (pin "P$10") (pinfunction "10_P$10") (pintype "passive"))
    )
    (net (code "31") (name "/SWD") (class "Default")
      (node (ref "IC2") (pin "34") (pinfunction "PA13_34") (pintype "bidirectional"))
      (node (ref "R64") (pin "2") (pinfunction "2_2") (pintype "passive"))
      (node (ref "U$12") (pin "P$8") (pinfunction "8_P$8") (pintype "passive"))
    )
    (net (code "32") (name "/TIME") (class "Default")
      (node (ref "IC2") (pin "42") (pinfunction "PB6_42") (pintype "bidirectional"))
      (node (ref "JP1") (pin "15") (pinfunction "15_15") (pintype "passive"))
    )
    (net (code "33") (name "/TX-S") (class "Default")
      (node (ref "IC2") (pin "30") (pinfunction "PA9_30") (pintype "bidirectional"))
      (node (ref "U$12") (pin "P$6") (pinfunction "6_P$6") (pintype "passive"))
    )
    (net (code "34") (name "/Y") (class "Default")
      (node (ref "INVERT") (pin "P$4") (pinfunction "Y_P$4") (pintype "bidirectional"))
      (node (ref "R57") (pin "1") (pinfunction "1_1") (pintype "passive"))
      (node (ref "U$23") (pin "18") (pinfunction "RUN_18") (pintype "bidirectional"))
    )
    (net (code "35") (name "Net-(3,3µH-Pad1)") (class "Default")
      (node (ref "3,3µH") (pin "1") (pinfunction "1_1") (pintype "bidirectional"))
      (node (ref "C41") (pin "1") (pinfunction "1_1") (pintype "passive"))
      (node (ref "U$59") (pin "5") (pinfunction "SW2_5") (pintype "bidirectional"))
      (node (ref "U$59") (pin "8") (pinfunction "SW2_8") (pintype "bidirectional"))
    )
    (net (code "36") (name "Net-(3,3µH-Pad2)") (class "Default")
      (node (ref "3,3µH") (pin "2") (pinfunction "2_2") (pintype "bidirectional"))
      (node (ref "C40") (pin "1") (pinfunction "1_1") (pintype "passive"))
      (node (ref "U$59") (pin "21") (pinfunction "SW1_21") (pintype "bidirectional"))
      (node (ref "U$59") (pin "24") (pinfunction "SW1_24") (pintype "bidirectional"))
    )
    (net (code "37") (name "Net-(3,3µH1-Pad1)") (class "Default")
      (node (ref "3,3µH1") (pin "1") (pinfunction "1_1") (pintype "bidirectional"))
      (node (ref "C50") (pin "1") (pinfunction "1_1") (pintype "passive"))
      (node (ref "U$23") (pin "5") (pinfunction "SW2_5") (pintype "bidirectional"))
      (node (ref "U$23") (pin "8") (pinfunction "SW2_8") (pintype "bidirectional"))
    )
    (net (code "38") (name "Net-(3,3µH1-Pad2)") (class "Default")
      (node (ref "3,3µH1") (pin "2") (pinfunction "2_2") (pintype "bidirectional"))
      (node (ref "C49") (pin "1") (pinfunction "1_1") (pintype "passive"))
      (node (ref "U$23") (pin "21") (pinfunction "SW1_21") (pintype "bidirectional"))
      (node (ref "U$23") (pin "24") (pinfunction "SW1_24") (pintype "bidirectional"))
    )
    (net (code "39") (name "Net-(AD5272#2-A)") (class "Default")
      (node (ref "AD5272#2") (pin "2") (pinfunction "A_2") (pintype "bidirectional"))
      (node (ref "R1") (pin "2") (pinfunction "2_2") (pintype "passive"))
      (node (ref "U$23") (pin "12") (pinfunction "FB_12") (pintype "bidirectional"))
    )
    (net (code "40") (name "Net-(AD5272#2-CAP)") (class "Default")
      (node (ref "AD5272#2") (pin "5") (pinfunction "CAP_5") (pintype "bidirectional"))
      (node (ref "C29") (pin "1") (pinfunction "1_1") (pintype "passive"))
    )
    (net (code "41") (name "Net-(AD5272#2-VDD)") (class "Default")
      (node (ref "AD5272#2") (pin "1") (pinfunction "VDD_1") (pintype "bidirectional"))
      (node (ref "C53") (pin "1") (pinfunction "1_1") (pintype "passive"))
      (node (ref "C56") (pin "1") (pinfunction "1_1") (pintype "passive"))
      (node (ref "C57") (pin "1") (pinfunction "1_1") (pintype "passive"))
      (node (ref "LED_G2") (pin "A") (pinfunction "A_A") (pintype "passive"))
      (node (ref "U$23") (pin "11") (pinfunction "SVCC_11") (pintype "bidirectional"))
      (node (ref "U$23") (pin "15") (pinfunction "MPPC_15") (pintype "bidirectional"))
      (node (ref "U$23") (pin "16") (pinfunction "VCC_16") (pintype "bidirectional"))
    )
    (net (code "42") (name "Net-(AD5272#2-VSS)") (class "Default")
      (node (ref "AD5272#2") (pin "3") (pinfunction "W_3") (pintype "bidirectional"))
      (node (ref "AD5272#2") (pin "4") (pinfunction "VSS_4") (pintype "bidirectional"))
      (node (ref "C29") (pin "2") (pinfunction "2_2") (pintype "passive"))
      (node (ref "R3") (pin "1") (pinfunction "1_1") (pintype "passive"))
    )
    (net (code "43") (name "Net-(C44-Pad1)") (class "Default")
      (node (ref "C44") (pin "1") (pinfunction "1_1") (pintype "passive"))
      (node (ref "R69") (pin "2") (pinfunction "2_2") (pintype "passive"))
    )
    (net (code "44") (name "Net-(C46-Pad1)") (class "Default")
      (node (ref "C46") (pin "1") (pinfunction "1_1") (pintype "passive"))
      (node (ref "R66") (pin "1") (pinfunction "1_1") (pintype "passive"))
    )
    (net (code "45") (name "Net-(C52-Pad1)") (class "Default")
      (node (ref "C52") (pin "1") (pinfunction "1_1") (pintype "passive"))
      (node (ref "R30") (pin "2") (pinfunction "2_2") (pintype "passive"))
    )
    (net (code "46") (name "Net-(IC2-OSC_IN)") (class "Default")
      (node (ref "C1") (pin "1") (pinfunction "1_1") (pintype "passive"))
      (node (ref "IC2") (pin "5") (pinfunction "OSC_IN_5") (pintype "bidirectional"))
    )
    (net (code "47") (name "Net-(IC2-PB5)") (class "Default")
      (node (ref "IC2") (pin "41") (pinfunction "PB5_41") (pintype "bidirectional"))
      (node (ref "R81") (pin "1") (pinfunction "1_1") (pintype "passive"))
    )
    (net (code "48") (name "Net-(INA219#1-IN+)") (class "Default")
      (node (ref "C9") (pin "1") (pinfunction "1_1") (pintype "passive"))
      (node (ref "INA219#1") (pin "1") (pinfunction "IN+_1") (pintype "bidirectional"))
      (node (ref "R73") (pin "2") (pinfunction "2_2") (pintype "passive"))
    )
    (net (code "49") (name "Net-(INA219#1-IN-)") (class "Default")
      (node (ref "C9") (pin "2") (pinfunction "2_2") (pintype "passive"))
      (node (ref "INA219#1") (pin "2") (pinfunction "IN-_2") (pintype "bidirectional"))
      (node (ref "R74") (pin "2") (pinfunction "2_2") (pintype "passive"))
    )
    (net (code "50") (name "Net-(LED_G1-PadC)") (class "Default")
      (node (ref "LED_G1") (pin "C") (pinfunction "C_C") (pintype "passive"))
      (node (ref "R100") (pin "2") (pinfunction "2_2") (pintype "passive"))
    )
    (net (code "51") (name "Net-(LED_G2-PadC)") (class "Default")
      (node (ref "LED_G2") (pin "C") (pinfunction "C_C") (pintype "passive"))
      (node (ref "R33") (pin "2") (pinfunction "2_2") (pintype "passive"))
    )
    (net (code "52") (name "Net-(LED_R1-PadA)") (class "Default")
      (node (ref "LED_R1") (pin "A") (pinfunction "A_A") (pintype "passive"))
      (node (ref "R32") (pin "2") (pinfunction "2_2") (pintype "passive"))
    )
    (net (code "53") (name "Net-(LED_R2-PadA)") (class "Default")
      (node (ref "LED_R2") (pin "A") (pinfunction "A_A") (pintype "passive"))
      (node (ref "R57") (pin "2") (pinfunction "2_2") (pintype "passive"))
    )
    (net (code "54") (name "Net-(OPA-IN-)") (class "Default")
      (node (ref "OPA") (pin "P$4") (pinfunction "IN-_P$4") (pintype "bidirectional"))
      (node (ref "R5") (pin "2") (pinfunction "WIPER_2") (pintype "passive"))
    )
    (net (code "55") (name "Net-(PB5-PadC)") (class "Default")
      (node (ref "PB5") (pin "C") (pinfunction "C_C") (pintype "passive"))
      (node (ref "R81") (pin "2") (pinfunction "2_2") (pintype "passive"))
    )
    (net (code "56") (name "Net-(PWR-PadC)") (class "Default")
      (node (ref "PWR") (pin "C") (pinfunction "C_C") (pintype "passive"))
      (node (ref "R82") (pin "2") (pinfunction "2_2") (pintype "passive"))
    )
    (net (code "57") (name "Net-(R6-WIPER)") (class "Default")
      (node (ref "R6") (pin "2") (pinfunction "WIPER_2") (pintype "passive"))
      (node (ref "U$59") (pin "12") (pinfunction "FB_12") (pintype "bidirectional"))
    )
    (net (code "58") (name "Net-(U$2-OUTPUT)") (class "Default")
      (node (ref "C1") (pin "2") (pinfunction "2_2") (pintype "passive"))
      (node (ref "U$2") (pin "P$3") (pinfunction "OUTPUT_P$3") (pintype "bidirectional"))
    )
    (net (code "59") (name "Net-(U$23-BST1)") (class "Default")
      (node (ref "C49") (pin "2") (pinfunction "2_2") (pintype "passive"))
      (node (ref "U$23") (pin "26") (pinfunction "BST1_26") (pintype "bidirectional"))
    )
    (net (code "60") (name "Net-(U$23-BST2)") (class "Default")
      (node (ref "C50") (pin "2") (pinfunction "2_2") (pintype "passive"))
      (node (ref "U$23") (pin "3") (pinfunction "BST2_3") (pintype "bidirectional"))
    )
    (net (code "61") (name "Net-(U$23-RT)") (class "Default")
      (node (ref "R28") (pin "2") (pinfunction "2_2") (pintype "passive"))
      (node (ref "U$23") (pin "17") (pinfunction "RT_17") (pintype "bidirectional"))
    )
    (net (code "62") (name "Net-(U$23-VC)") (class "Default")
      (node (ref "R30") (pin "1") (pinfunction "1_1") (pintype "passive"))
      (node (ref "U$23") (pin "13") (pinfunction "VC_13") (pintype "bidirectional"))
    )
    (net (code "63") (name "Net-(U$57-IN+)") (class "Default")
      (node (ref "C10") (pin "1") (pinfunction "1_1") (pintype "passive"))
      (node (ref "R76") (pin "2") (pinfunction "2_2") (pintype "passive"))
      (node (ref "U$57") (pin "1") (pinfunction "IN+_1") (pintype "bidirectional"))
    )
    (net (code "64") (name "Net-(U$57-IN-)") (class "Default")
      (node (ref "C10") (pin "2") (pinfunction "2_2") (pintype "passive"))
      (node (ref "R77") (pin "2") (pinfunction "2_2") (pintype "passive"))
      (node (ref "U$57") (pin "2") (pinfunction "IN-_2") (pintype "bidirectional"))
    )
    (net (code "65") (name "Net-(U$59-BST1)") (class "Default")
      (node (ref "C40") (pin "2") (pinfunction "2_2") (pintype "passive"))
      (node (ref "U$59") (pin "26") (pinfunction "BST1_26") (pintype "bidirectional"))
    )
    (net (code "66") (name "Net-(U$59-BST2)") (class "Default")
      (node (ref "C41") (pin "2") (pinfunction "2_2") (pintype "passive"))
      (node (ref "U$59") (pin "3") (pinfunction "BST2_3") (pintype "bidirectional"))
    )
    (net (code "67") (name "Net-(U$59-MPPC)") (class "Default")
      (node (ref "R65") (pin "1") (pinfunction "1_1") (pintype "passive"))
      (node (ref "R66") (pin "2") (pinfunction "2_2") (pintype "passive"))
      (node (ref "R67") (pin "2") (pinfunction "2_2") (pintype "passive"))
      (node (ref "U$59") (pin "15") (pinfunction "MPPC_15") (pintype "bidirectional"))
    )
    (net (code "68") (name "Net-(U$59-RT)") (class "Default")
      (node (ref "R68") (pin "2") (pinfunction "2_2") (pintype "passive"))
      (node (ref "U$59") (pin "17") (pinfunction "RT_17") (pintype "bidirectional"))
    )
    (net (code "69") (name "Net-(U$59-SVCC)") (class "Default")
      (node (ref "C45") (pin "1") (pinfunction "1_1") (pintype "passive"))
      (node (ref "LED_G1") (pin "A") (pinfunction "A_A") (pintype "passive"))
      (node (ref "U$59") (pin "11") (pinfunction "SVCC_11") (pintype "bidirectional"))
      (node (ref "U$59") (pin "16") (pinfunction "VCC_16") (pintype "bidirectional"))
    )
    (net (code "70") (name "Net-(U$59-VC)") (class "Default")
      (node (ref "R69") (pin "1") (pinfunction "1_1") (pintype "passive"))
      (node (ref "U$59") (pin "13") (pinfunction "VC_13") (pintype "bidirectional"))
    )
    (net (code "71") (name "unconnected-(IC2-OSC_OUT-Pad6)") (class "Default")
      (node (ref "IC2") (pin "6") (pinfunction "OSC_OUT_6") (pintype "bidirectional"))
    )
    (net (code "72") (name "unconnected-(IC2-PA0-WKUP-Pad10)") (class "Default")
      (node (ref "IC2") (pin "10") (pinfunction "PA0-WKUP_10") (pintype "bidirectional"))
    )
    (net (code "73") (name "unconnected-(IC2-PA8-Pad29)") (class "Default")
      (node (ref "IC2") (pin "29") (pinfunction "PA8_29") (pintype "bidirectional"))
    )
    (net (code "74") (name "unconnected-(IC2-PA11-Pad32)") (class "Default")
      (node (ref "IC2") (pin "32") (pinfunction "PA11_32") (pintype "bidirectional"))
    )
    (net (code "75") (name "unconnected-(IC2-PA12-Pad33)") (class "Default")
      (node (ref "IC2") (pin "33") (pinfunction "PA12_33") (pintype "bidirectional"))
    )
    (net (code "76") (name "unconnected-(IC2-PA15-Pad38)") (class "Default")
      (node (ref "IC2") (pin "38") (pinfunction "PA15_38") (pintype "bidirectional"))
    )
    (net (code "77") (name "unconnected-(IC2-PB3-Pad39)") (class "Default")
      (node (ref "IC2") (pin "39") (pinfunction "PB3_39") (pintype "bidirectional"))
    )
    (net (code "78") (name "unconnected-(IC2-PB4-Pad40)") (class "Default")
      (node (ref "IC2") (pin "40") (pinfunction "PB4_40") (pintype "bidirectional"))
    )
    (net (code "79") (name "unconnected-(IC2-PB7-Pad43)") (class "Default")
      (node (ref "IC2") (pin "43") (pinfunction "PB7_43") (pintype "bidirectional"))
    )
    (net (code "80") (name "unconnected-(IC2-PB12-Pad25)") (class "Default")
      (node (ref "IC2") (pin "25") (pinfunction "PB12_25") (pintype "bidirectional"))
    )
    (net (code "81") (name "unconnected-(IC2-PB13-Pad26)") (class "Default")
      (node (ref "IC2") (pin "26") (pinfunction "PB13_26") (pintype "bidirectional"))
    )
    (net (code "82") (name "unconnected-(IC2-PB14-Pad27)") (class "Default")
      (node (ref "IC2") (pin "27") (pinfunction "PB14_27") (pintype "bidirectional"))
    )
    (net (code "83") (name "unconnected-(IC2-PC13-Pad2)") (class "Default")
      (node (ref "IC2") (pin "2") (pinfunction "PC13_2") (pintype "bidirectional"))
    )
    (net (code "84") (name "unconnected-(IC2-PC14-Pad3)") (class "Default")
      (node (ref "IC2") (pin "3") (pinfunction "PC14_3") (pintype "bidirectional"))
    )
    (net (code "85") (name "unconnected-(IC2-PC15-Pad4)") (class "Default")
      (node (ref "IC2") (pin "4") (pinfunction "PC15_4") (pintype "bidirectional"))
    )
    (net (code "86") (name "unconnected-(INVERT-NC-PadP$1)") (class "Default")
      (node (ref "INVERT") (pin "P$1") (pinfunction "NC_P$1") (pintype "bidirectional"))
    )
    (net (code "87") (name "unconnected-(U$2-STANDBY-PadP$1)") (class "Default")
      (node (ref "U$2") (pin "P$1") (pinfunction "STANDBY_P$1") (pintype "bidirectional"))
    )
    (net (code "88") (name "unconnected-(U$12-12-PadP$12)") (class "Default")
      (node (ref "U$12") (pin "P$12") (pinfunction "12_P$12") (pintype "passive"))
    )
    (net (code "89") (name "unconnected-(U$12-13-PadP$13)") (class "Default")
      (node (ref "U$12") (pin "P$13") (pinfunction "13_P$13") (pintype "passive"))
    )
    (net (code "90") (name "unconnected-(U$12-14-PadP$14)") (class "Default")
      (node (ref "U$12") (pin "P$14") (pinfunction "14_P$14") (pintype "passive"))
    )
    (net (code "91") (name "unconnected-(U$12-15-PadP$15)") (class "Default")
      (node (ref "U$12") (pin "P$15") (pinfunction "15_P$15") (pintype "passive"))
    )
  )
)
